# ESP8266-07_SAMD21.net
KiCad netlist of a schematic drawn in EAGLE
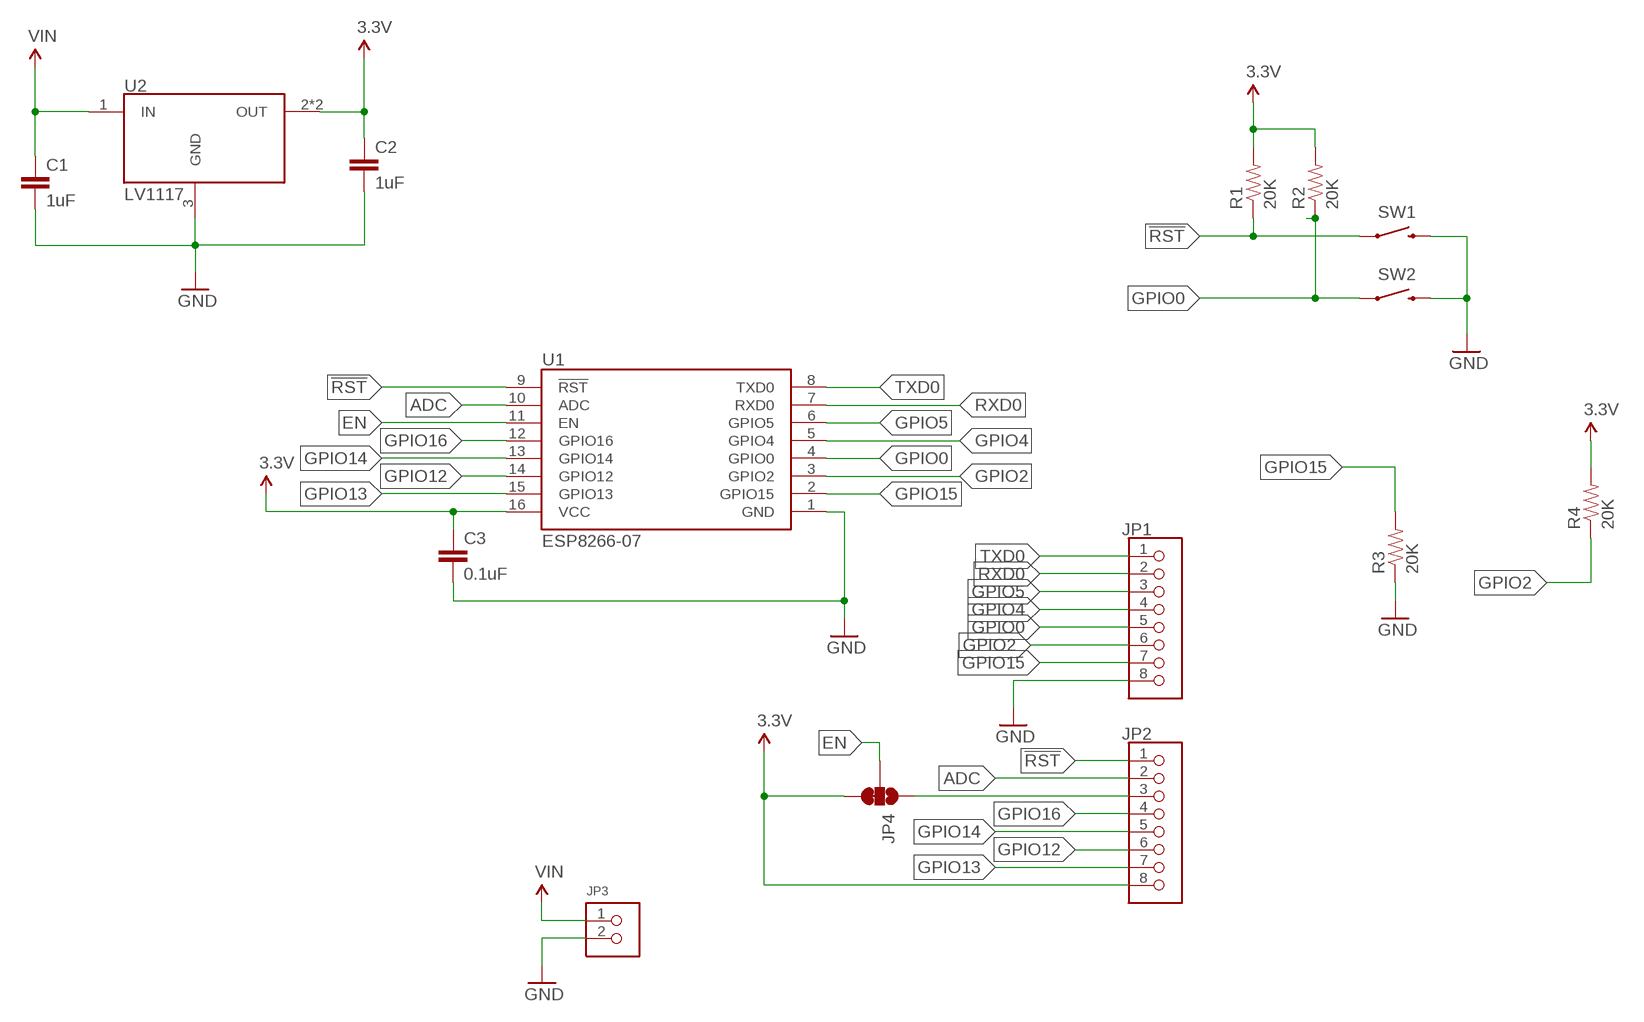
[diagram p0: schematic, sheet 1]

(export (version "E")
  (design (tool "Eeschema 10.0.6"))
  (components
    (comp (ref "C1")
      (value "1uF")
      (footprint "eagle-import:C0603")
      (libsource (lib "eagle-import") (part "C0603"))
    )
    (comp (ref "C2")
      (value "1uF")
      (footprint "eagle-import:C0603")
      (libsource (lib "eagle-import") (part "C0603"))
    )
    (comp (ref "C3")
      (value "0.1uF")
      (footprint "eagle-import:C0603")
      (libsource (lib "eagle-import") (part "C0603"))
    )
    (comp (ref "JP1")
      (value "HEADER_1X8_100MIL_PTH")
      (footprint "eagle-import:HEADER_100MIL_1X8")
      (libsource (lib "eagle-import") (part "HEADER_1X8_100MIL_PTH"))
    )
    (comp (ref "JP2")
      (value "HEADER_1X8_100MIL_PTH")
      (footprint "eagle-import:HEADER_100MIL_1X8")
      (libsource (lib "eagle-import") (part "HEADER_1X8_100MIL_PTH"))
    )
    (comp (ref "JP3")
      (value "HEADER_1X2_100MIL")
      (footprint "eagle-import:HEADER_100MIL_1X2")
      (libsource (lib "eagle-import") (part "HEADER_1X2_100MIL"))
    )
    (comp (ref "JP4")
      (value "JUMPER-PAD-3-2OF3_NC_BY_TRACE")
      (footprint "eagle-import:PAD-JUMPER-3-2OF3_NC_BY_TRACE_YES_SILK_FULL_BOX")
      (libsource (lib "eagle-import") (part "JUMPER-PAD-3-2OF3_NC_BY_TRACE"))
    )
    (comp (ref "R1")
      (value "20K")
      (footprint "eagle-import:R0603")
      (libsource (lib "eagle-import") (part "R0603"))
    )
    (comp (ref "R2")
      (value "20K")
      (footprint "eagle-import:R0603")
      (libsource (lib "eagle-import") (part "R0603"))
    )
    (comp (ref "R3")
      (value "20K")
      (footprint "eagle-import:R0603")
      (libsource (lib "eagle-import") (part "R0603"))
    )
    (comp (ref "R4")
      (value "20K")
      (footprint "eagle-import:R0603")
      (libsource (lib "eagle-import") (part "R0603"))
    )
    (comp (ref "SW1")
      (value "KMR221GLFS")
      (footprint "eagle-import:TACTILE_SWITCH_SMD-3")
      (libsource (lib "eagle-import") (part "KMR221GLFS"))
    )
    (comp (ref "SW2")
      (value "KMR221GLFS")
      (footprint "eagle-import:TACTILE_SWITCH_SMD-3")
      (libsource (lib "eagle-import") (part "KMR221GLFS"))
    )
    (comp (ref "U1")
      (value "ESP8266-07")
      (footprint "eagle-import:ESP8266-07")
      (libsource (lib "eagle-import") (part "ESP8266-07"))
    )
    (comp (ref "U2")
      (value "TLV1114DCY")
      (footprint "eagle-import:SOT223")
      (libsource (lib "eagle-import") (part "TLV1114DCY"))
    )
  )
  (nets
    (net (code "1") (name "/~{RST}") (class "Default")
      (node (ref "JP2") (pin "1") (pinfunction "1_1") (pintype "passive"))
      (node (ref "R1") (pin "1") (pinfunction "1_1") (pintype "passive"))
      (node (ref "SW1") (pin "1") (pinfunction "1_1") (pintype "passive"))
      (node (ref "SW1") (pin "2") (pinfunction "1_2") (pintype "passive"))
      (node (ref "U1") (pin "9") (pinfunction "~{RST}_9") (pintype "input"))
    )
    (net (code "2") (name "3.3V") (class "Default")
      (node (ref "C2") (pin "1") (pinfunction "1_1") (pintype "passive"))
      (node (ref "C3") (pin "1") (pinfunction "1_1") (pintype "passive"))
      (node (ref "JP2") (pin "8") (pinfunction "8_8") (pintype "passive"))
      (node (ref "JP4") (pin "3") (pinfunction "3_3") (pintype "passive"))
      (node (ref "R1") (pin "2") (pinfunction "2_2") (pintype "passive"))
      (node (ref "R2") (pin "2") (pinfunction "2_2") (pintype "passive"))
      (node (ref "R4") (pin "2") (pinfunction "2_2") (pintype "passive"))
      (node (ref "U1") (pin "16") (pinfunction "VCC_16") (pintype "power_in"))
      (node (ref "U2") (pin "2") (pinfunction "OUT_2") (pintype "power_in"))
      (node (ref "U2") (pin "TAB") (pinfunction "OUT_TAB") (pintype "power_in"))
    )
    (net (code "3") (name "ADC") (class "Default")
      (node (ref "JP2") (pin "2") (pinfunction "2_2") (pintype "passive"))
      (node (ref "U1") (pin "10") (pinfunction "ADC_10") (pintype "input"))
    )
    (net (code "4") (name "EN") (class "Default")
      (node (ref "JP4") (pin "2") (pinfunction "2_2") (pintype "passive"))
      (node (ref "U1") (pin "11") (pinfunction "EN_11") (pintype "input"))
    )
    (net (code "5") (name "GND") (class "Default")
      (node (ref "C1") (pin "2") (pinfunction "2_2") (pintype "passive"))
      (node (ref "C2") (pin "2") (pinfunction "2_2") (pintype "passive"))
      (node (ref "C3") (pin "2") (pinfunction "2_2") (pintype "passive"))
      (node (ref "JP1") (pin "8") (pinfunction "8_8") (pintype "passive"))
      (node (ref "JP3") (pin "2") (pinfunction "2_2") (pintype "passive"))
      (node (ref "R3") (pin "1") (pinfunction "1_1") (pintype "passive"))
      (node (ref "SW1") (pin "3") (pinfunction "2_3") (pintype "passive"))
      (node (ref "SW1") (pin "4") (pinfunction "2_4") (pintype "passive"))
      (node (ref "SW2") (pin "3") (pinfunction "2_3") (pintype "passive"))
      (node (ref "SW2") (pin "4") (pinfunction "2_4") (pintype "passive"))
      (node (ref "U1") (pin "1") (pinfunction "GND_1") (pintype "power_in"))
      (node (ref "U2") (pin "3") (pinfunction "GND_3") (pintype "power_in"))
    )
    (net (code "6") (name "GPIO0") (class "Default")
      (node (ref "JP1") (pin "5") (pinfunction "5_5") (pintype "passive"))
      (node (ref "R2") (pin "1") (pinfunction "1_1") (pintype "passive"))
      (node (ref "SW2") (pin "1") (pinfunction "1_1") (pintype "passive"))
      (node (ref "SW2") (pin "2") (pinfunction "1_2") (pintype "passive"))
      (node (ref "U1") (pin "4") (pinfunction "GPIO0_4") (pintype "bidirectional"))
    )
    (net (code "7") (name "GPIO2") (class "Default")
      (node (ref "JP1") (pin "6") (pinfunction "6_6") (pintype "passive"))
      (node (ref "R4") (pin "1") (pinfunction "1_1") (pintype "passive"))
      (node (ref "U1") (pin "3") (pinfunction "GPIO2_3") (pintype "bidirectional"))
    )
    (net (code "8") (name "GPIO4") (class "Default")
      (node (ref "JP1") (pin "4") (pinfunction "4_4") (pintype "passive"))
      (node (ref "U1") (pin "5") (pinfunction "GPIO4_5") (pintype "bidirectional"))
    )
    (net (code "9") (name "GPIO5") (class "Default")
      (node (ref "JP1") (pin "3") (pinfunction "3_3") (pintype "passive"))
      (node (ref "U1") (pin "6") (pinfunction "GPIO5_6") (pintype "bidirectional"))
    )
    (net (code "10") (name "GPIO12") (class "Default")
      (node (ref "JP2") (pin "6") (pinfunction "6_6") (pintype "passive"))
      (node (ref "U1") (pin "14") (pinfunction "GPIO12_14") (pintype "bidirectional"))
    )
    (net (code "11") (name "GPIO13") (class "Default")
      (node (ref "JP2") (pin "7") (pinfunction "7_7") (pintype "passive"))
      (node (ref "U1") (pin "15") (pinfunction "GPIO13_15") (pintype "bidirectional"))
    )
    (net (code "12") (name "GPIO14") (class "Default")
      (node (ref "JP2") (pin "5") (pinfunction "5_5") (pintype "passive"))
      (node (ref "U1") (pin "13") (pinfunction "GPIO14_13") (pintype "bidirectional"))
    )
    (net (code "13") (name "GPIO15") (class "Default")
      (node (ref "JP1") (pin "7") (pinfunction "7_7") (pintype "passive"))
      (node (ref "R3") (pin "2") (pinfunction "2_2") (pintype "passive"))
      (node (ref "U1") (pin "2") (pinfunction "GPIO15_2") (pintype "bidirectional"))
    )
    (net (code "14") (name "GPIO16") (class "Default")
      (node (ref "JP2") (pin "4") (pinfunction "4_4") (pintype "passive"))
      (node (ref "U1") (pin "12") (pinfunction "GPIO16_12") (pintype "bidirectional"))
    )
    (net (code "15") (name "Net-(JP2-Pad3)") (class "Default")
      (node (ref "JP2") (pin "3") (pinfunction "3_3") (pintype "passive"))
      (node (ref "JP4") (pin "1") (pinfunction "1_1") (pintype "passive"))
    )
    (net (code "16") (name "RXD0") (class "Default")
      (node (ref "JP1") (pin "2") (pinfunction "2_2") (pintype "passive"))
      (node (ref "U1") (pin "7") (pinfunction "RXD0_7") (pintype "input"))
    )
    (net (code "17") (name "TXD0") (class "Default")
      (node (ref "JP1") (pin "1") (pinfunction "1_1") (pintype "passive"))
      (node (ref "U1") (pin "8") (pinfunction "TXD0_8") (pintype "output"))
    )
    (net (code "18") (name "VIN") (class "Default")
      (node (ref "C1") (pin "1") (pinfunction "1_1") (pintype "passive"))
      (node (ref "JP3") (pin "1") (pinfunction "1_1") (pintype "passive"))
      (node (ref "U2") (pin "1") (pinfunction "IN_1") (pintype "power_in"))
    )
  )
)
